# TopLevelSchem.net
KiCad netlist of a schematic drawn in Altium Designer
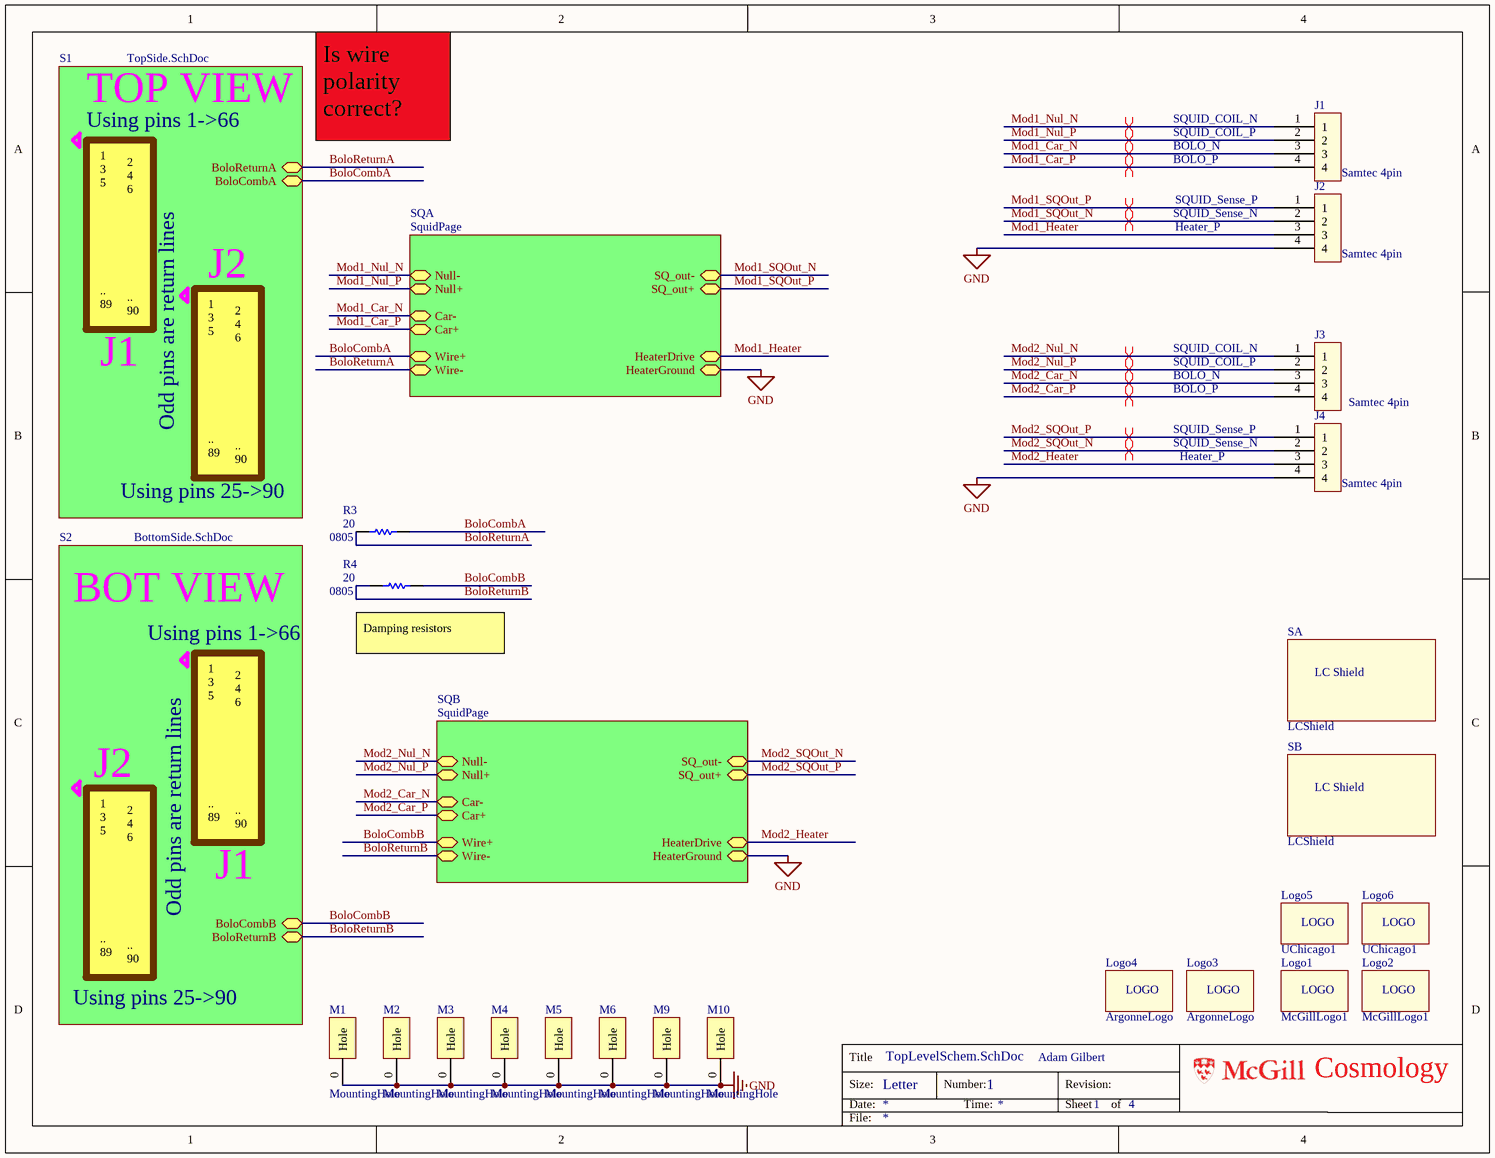
[diagram p0: TopLevelSchem.SchDoc]

(export (version "E")
  (design (tool "Eeschema 10.0.6"))
  (components
    (comp (ref "J1")
      (value "Samtec 4pin")
      (footprint "Samtec4pin")
      (libsource (lib "SPT3G_LCBoard") (part "Samtec4pin"))
    )
    (comp (ref "J2")
      (value "Samtec 4pin")
      (footprint "Samtec4pin")
      (libsource (lib "SPT3G_LCBoard") (part "Samtec4pin"))
    )
    (comp (ref "J3")
      (value "Samtec 4pin")
      (footprint "Samtec4pin")
      (libsource (lib "SPT3G_LCBoard") (part "Samtec4pin"))
    )
    (comp (ref "J4")
      (value "Samtec 4pin")
      (footprint "Samtec4pin")
      (libsource (lib "SPT3G_LCBoard") (part "Samtec4pin"))
    )
    (comp (ref "Logo1")
      (value "McGillLogo1")
      (footprint "McGillLogo1")
      (libsource (lib "SPT3G_LCBoard") (part "Logo"))
    )
    (comp (ref "Logo2")
      (value "McGillLogo1")
      (footprint "McGillLogo1")
      (libsource (lib "SPT3G_LCBoard") (part "Logo"))
    )
    (comp (ref "Logo3")
      (value "ArgonneLogo")
      (footprint "ArgonneLogo")
      (libsource (lib "SPT3G_AdapterBoard") (part "Logo"))
    )
    (comp (ref "Logo4")
      (value "ArgonneLogo")
      (footprint "ArgonneLogo")
      (libsource (lib "SPT3G_AdapterBoard") (part "Logo"))
    )
    (comp (ref "Logo5")
      (value "UChicago1")
      (footprint "UChicagoLogo")
      (libsource (lib "SPT3G_LCBoard") (part "Logo"))
    )
    (comp (ref "Logo6")
      (value "UChicago1")
      (footprint "UChicagoLogo")
      (libsource (lib "SPT3G_LCBoard") (part "Logo"))
    )
    (comp (ref "M1")
      (value "MountingHole")
      (footprint "MountingHole")
      (libsource (lib "SPT3G_LCBoard") (part "MountingHole"))
    )
    (comp (ref "M2")
      (value "MountingHole")
      (footprint "MountingHole")
      (libsource (lib "SPT3G_LCBoard") (part "MountingHole"))
    )
    (comp (ref "M3")
      (value "MountingHole")
      (footprint "MountingHole")
      (libsource (lib "SPT3G_LCBoard") (part "MountingHole"))
    )
    (comp (ref "M4")
      (value "MountingHole")
      (footprint "MountingHole")
      (libsource (lib "SPT3G_LCBoard") (part "MountingHole"))
    )
    (comp (ref "M5")
      (value "MountingHole")
      (footprint "MountingHole")
      (libsource (lib "SPT3G_LCBoard") (part "MountingHole"))
    )
    (comp (ref "M6")
      (value "MountingHole")
      (footprint "MountingHole")
      (libsource (lib "SPT3G_LCBoard") (part "MountingHole"))
    )
    (comp (ref "M9")
      (value "MountingHole")
      (footprint "MountingHole")
      (libsource (lib "SPT3G_LCBoard") (part "MountingHole"))
    )
    (comp (ref "M10")
      (value "MountingHole")
      (footprint "MountingHole")
      (libsource (lib "SPT3G_LCBoard") (part "MountingHole"))
    )
    (comp (ref "R3")
      (value "20")
      (footprint "0805")
      (description "Resistor")
      (libsource (lib "SPT3G_LCBoard") (part "Res1206"))
    )
    (comp (ref "R4")
      (value "20")
      (footprint "0805")
      (description "Resistor")
      (libsource (lib "SPT3G_LCBoard") (part "Res1206"))
    )
    (comp (ref "SA")
      (value "LCShield")
      (footprint "LCShield")
      (libsource (lib "SPT3G_LCBoard") (part "LCShield"))
    )
    (comp (ref "SB")
      (value "LCShield")
      (footprint "LCShield")
      (libsource (lib "SPT3G_LCBoard") (part "LCShield"))
    )
  )
  (nets
    (net (code "1") (name "/BoloCombA") (class "Default")
      (node (ref "R3") (pin "1") (pinfunction "1_1") (pintype "passive"))
    )
    (net (code "2") (name "/BoloCombB") (class "Default")
      (node (ref "R4") (pin "1") (pinfunction "1_1") (pintype "passive"))
    )
    (net (code "3") (name "/BoloReturnA") (class "Default")
      (node (ref "R3") (pin "2") (pinfunction "2_2") (pintype "passive"))
    )
    (net (code "4") (name "/BoloReturnB") (class "Default")
      (node (ref "R4") (pin "2") (pinfunction "2_2") (pintype "passive"))
    )
    (net (code "5") (name "/Mod1_Car_N") (class "Default")
      (node (ref "J1") (pin "3") (pinfunction "3_3") (pintype "passive"))
    )
    (net (code "6") (name "/Mod1_Car_P") (class "Default")
      (node (ref "J1") (pin "4") (pinfunction "4_4") (pintype "passive"))
    )
    (net (code "7") (name "/Mod1_Heater") (class "Default")
      (node (ref "J2") (pin "3") (pinfunction "3_3") (pintype "passive"))
    )
    (net (code "8") (name "/Mod1_Nul_N") (class "Default")
      (node (ref "J1") (pin "1") (pinfunction "1_1") (pintype "passive"))
    )
    (net (code "9") (name "/Mod1_Nul_P") (class "Default")
      (node (ref "J1") (pin "2") (pinfunction "2_2") (pintype "passive"))
    )
    (net (code "10") (name "/Mod1_SQOut_N") (class "Default")
      (node (ref "J2") (pin "2") (pinfunction "2_2") (pintype "passive"))
    )
    (net (code "11") (name "/Mod1_SQOut_P") (class "Default")
      (node (ref "J2") (pin "1") (pinfunction "1_1") (pintype "passive"))
    )
    (net (code "12") (name "/Mod2_Car_N") (class "Default")
      (node (ref "J3") (pin "3") (pinfunction "3_3") (pintype "passive"))
    )
    (net (code "13") (name "/Mod2_Car_P") (class "Default")
      (node (ref "J3") (pin "4") (pinfunction "4_4") (pintype "passive"))
    )
    (net (code "14") (name "/Mod2_Heater") (class "Default")
      (node (ref "J4") (pin "3") (pinfunction "3_3") (pintype "passive"))
    )
    (net (code "15") (name "/Mod2_Nul_N") (class "Default")
      (node (ref "J3") (pin "1") (pinfunction "1_1") (pintype "passive"))
    )
    (net (code "16") (name "/Mod2_Nul_P") (class "Default")
      (node (ref "J3") (pin "2") (pinfunction "2_2") (pintype "passive"))
    )
    (net (code "17") (name "/Mod2_SQOut_N") (class "Default")
      (node (ref "J4") (pin "2") (pinfunction "2_2") (pintype "passive"))
    )
    (net (code "18") (name "/Mod2_SQOut_P") (class "Default")
      (node (ref "J4") (pin "1") (pinfunction "1_1") (pintype "passive"))
    )
    (net (code "19") (name "GND") (class "Default")
      (node (ref "J2") (pin "4") (pinfunction "4_4") (pintype "passive"))
      (node (ref "J4") (pin "4") (pinfunction "4_4") (pintype "passive"))
      (node (ref "M1") (pin "0") (pinfunction "Hole_0") (pintype "passive"))
      (node (ref "M10") (pin "0") (pinfunction "Hole_0") (pintype "passive"))
      (node (ref "M2") (pin "0") (pinfunction "Hole_0") (pintype "passive"))
      (node (ref "M3") (pin "0") (pinfunction "Hole_0") (pintype "passive"))
      (node (ref "M4") (pin "0") (pinfunction "Hole_0") (pintype "passive"))
      (node (ref "M5") (pin "0") (pinfunction "Hole_0") (pintype "passive"))
      (node (ref "M6") (pin "0") (pinfunction "Hole_0") (pintype "passive"))
      (node (ref "M9") (pin "0") (pinfunction "Hole_0") (pintype "passive"))
    )
  )
)
